# 08-AD9513-1.net
KiCad netlist of a schematic drawn in Altium Designer
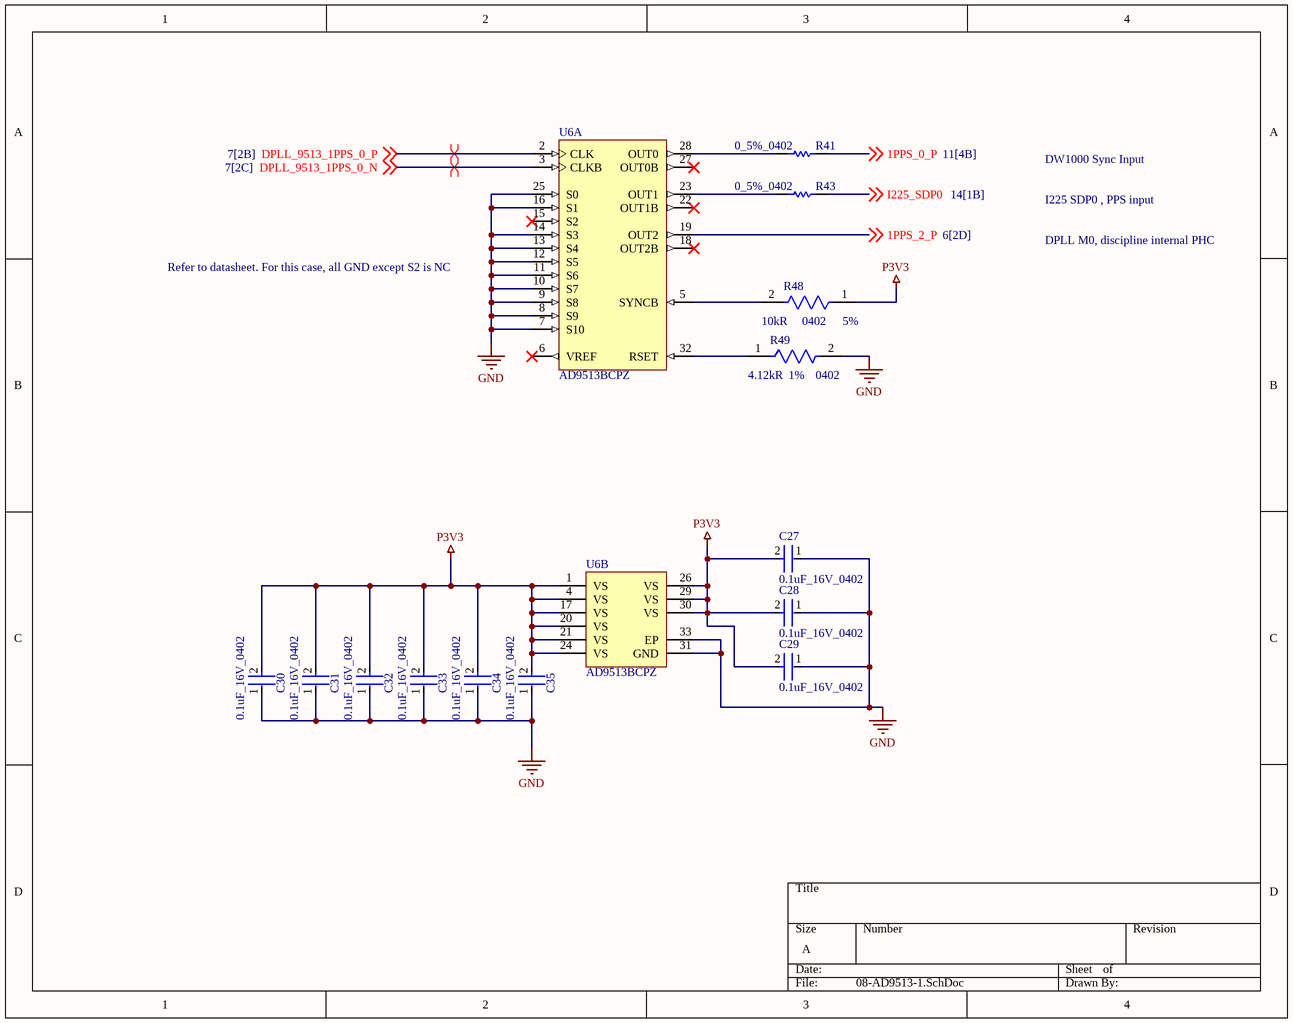
[diagram p0: 08-AD9513-1.SchDoc]

(export (version "E")
  (design (tool "Eeschema 10.0.6"))
  (components
    (comp (ref "C27")
      (value "0.1uF_16V_0402")
      (footprint "FP-GRM15-MFG")
      (description "CAP CER 0.1UF 16V X7R 0402")
      (fields (field (name "MANUFACTURER PART NUMBER") "GRM155R71C104KA88D") (field (name "TOLERANCE") "10%"))
      (libsource (lib "Altium Content Vault") (part "236180d848d6139a670b325ea6854c9"))
    )
    (comp (ref "C28")
      (value "0.1uF_16V_0402")
      (footprint "FP-GRM15-MFG")
      (description "CAP CER 0.1UF 16V X7R 0402")
      (fields (field (name "MANUFACTURER PART NUMBER") "GRM155R71C104KA88D") (field (name "TOLERANCE") "10%"))
      (libsource (lib "Altium Content Vault") (part "236180d848d6139a670b325ea6854c9"))
    )
    (comp (ref "C29")
      (value "0.1uF_16V_0402")
      (footprint "FP-GRM15-MFG")
      (description "CAP CER 0.1UF 16V X7R 0402")
      (fields (field (name "MANUFACTURER PART NUMBER") "GRM155R71C104KA88D") (field (name "TOLERANCE") "10%"))
      (libsource (lib "Altium Content Vault") (part "236180d848d6139a670b325ea6854c9"))
    )
    (comp (ref "C30")
      (value "0.1uF_16V_0402")
      (footprint "FP-GRM15-MFG")
      (description "CAP CER 0.1UF 16V X7R 0402")
      (fields (field (name "MANUFACTURER PART NUMBER") "GRM155R71C104KA88D") (field (name "TOLERANCE") "10%"))
      (libsource (lib "Altium Content Vault") (part "236180d848d6139a670b325ea6854c9"))
    )
    (comp (ref "C31")
      (value "0.1uF_16V_0402")
      (footprint "FP-GRM15-MFG")
      (description "CAP CER 0.1UF 16V X7R 0402")
      (fields (field (name "MANUFACTURER PART NUMBER") "GRM155R71C104KA88D") (field (name "TOLERANCE") "10%"))
      (libsource (lib "Altium Content Vault") (part "236180d848d6139a670b325ea6854c9"))
    )
    (comp (ref "C32")
      (value "0.1uF_16V_0402")
      (footprint "FP-GRM15-MFG")
      (description "CAP CER 0.1UF 16V X7R 0402")
      (fields (field (name "MANUFACTURER PART NUMBER") "GRM155R71C104KA88D") (field (name "TOLERANCE") "10%"))
      (libsource (lib "Altium Content Vault") (part "236180d848d6139a670b325ea6854c9"))
    )
    (comp (ref "C33")
      (value "0.1uF_16V_0402")
      (footprint "FP-GRM15-MFG")
      (description "CAP CER 0.1UF 16V X7R 0402")
      (fields (field (name "MANUFACTURER PART NUMBER") "GRM155R71C104KA88D") (field (name "TOLERANCE") "10%"))
      (libsource (lib "Altium Content Vault") (part "236180d848d6139a670b325ea6854c9"))
    )
    (comp (ref "C34")
      (value "0.1uF_16V_0402")
      (footprint "FP-GRM15-MFG")
      (description "CAP CER 0.1UF 16V X7R 0402")
      (fields (field (name "MANUFACTURER PART NUMBER") "GRM155R71C104KA88D") (field (name "TOLERANCE") "10%"))
      (libsource (lib "Altium Content Vault") (part "236180d848d6139a670b325ea6854c9"))
    )
    (comp (ref "C35")
      (value "0.1uF_16V_0402")
      (footprint "FP-GRM15-MFG")
      (description "CAP CER 0.1UF 16V X7R 0402")
      (fields (field (name "MANUFACTURER PART NUMBER") "GRM155R71C104KA88D") (field (name "TOLERANCE") "10%"))
      (libsource (lib "Altium Content Vault") (part "236180d848d6139a670b325ea6854c9"))
    )
    (comp (ref "R41")
      (value "0_5%_0402")
      (footprint "RESC1005X40X25LL10T10")
      (fields (field (name "MANUFACTURER") "KOA Speer") (field (name "PART NUMBER") "RK73Z1ETTP"))
      (libsource (lib "Altium Content Vault") (part "RES"))
    )
    (comp (ref "R43")
      (value "0_5%_0402")
      (footprint "RESC1005X40X25LL10T10")
      (fields (field (name "MANUFACTURER") "KOA Speer") (field (name "PART NUMBER") "RK73Z1ETTP"))
      (libsource (lib "Altium Content Vault") (part "RES"))
    )
    (comp (ref "R48")
      (value "CRCW040210K0JNED")
      (footprint "FP-CRCW0402-e3-IPC_B")
      (description "RES Thick Film, 10kΩ, 5%, 0.063W, 200ppm/°C, 0402")
      (fields
        (field (name "CASE/PACKAGE") "0402")
        (field (name "RESISTANCE") "10kR")
        (field (name "TOLERANCE") "5%")
      )
      (libsource (lib "Altium Content Vault") (part "1029c3af85768c4190bb7ad29bc67b5"))
    )
    (comp (ref "R49")
      (value "CRCW04024K12FKED")
      (footprint "FP-CRCW0402-e3-IPC_A")
      (description "RES Thick Film, 4.12kΩ, 1%, 0.063W, 100ppm/°C, 0402")
      (fields
        (field (name "RESISTANCE") "4.12kR")
        (field (name "CASE/PACKAGE") "0402")
        (field (name "TOLERANCE") "1%")
      )
      (libsource (lib "Altium Content Vault") (part "1029c3af85768c4190bb7ad29bc67b5"))
    )
    (comp (ref "U6")
      (value "AD9513BCPZ")
      (footprint "ADI-CP-32-2_N")
      (fields (field (name "MANUFACTURER") "Analog Devices"))
      (libsource (lib "Altium Content Vault") (part "ADI-AD9513-CP-32-2"))
    )
  )
  (nets
    (net (code "1") (name "1PPS_0_P") (class "Default")
      (node (ref "R41") (pin "2") (pinfunction "2_2") (pintype "passive"))
    )
    (net (code "2") (name "1PPS_2_P") (class "Default")
      (node (ref "U6") (pin "19") (pinfunction "OUT2_19") (pintype "output"))
    )
    (net (code "3") (name "DPLL_9513_1PPS_0_N") (class "Default")
      (node (ref "U6") (pin "3") (pinfunction "CLKB_3") (pintype "input"))
    )
    (net (code "4") (name "DPLL_9513_1PPS_0_P") (class "Default")
      (node (ref "U6") (pin "2") (pinfunction "CLK_2") (pintype "input"))
    )
    (net (code "5") (name "GND") (class "Default")
      (node (ref "C27") (pin "1") (pinfunction "1_1") (pintype "passive"))
      (node (ref "C28") (pin "1") (pinfunction "1_1") (pintype "passive"))
      (node (ref "C29") (pin "1") (pinfunction "1_1") (pintype "passive"))
      (node (ref "C30") (pin "1") (pinfunction "1_1") (pintype "passive"))
      (node (ref "C31") (pin "1") (pinfunction "1_1") (pintype "passive"))
      (node (ref "C32") (pin "1") (pinfunction "1_1") (pintype "passive"))
      (node (ref "C33") (pin "1") (pinfunction "1_1") (pintype "passive"))
      (node (ref "C34") (pin "1") (pinfunction "1_1") (pintype "passive"))
      (node (ref "C35") (pin "1") (pinfunction "1_1") (pintype "passive"))
      (node (ref "R49") (pin "2") (pinfunction "2_2") (pintype "passive"))
      (node (ref "U6") (pin "10") (pinfunction "S7_10") (pintype "input"))
      (node (ref "U6") (pin "11") (pinfunction "S6_11") (pintype "input"))
      (node (ref "U6") (pin "12") (pinfunction "S5_12") (pintype "input"))
      (node (ref "U6") (pin "13") (pinfunction "S4_13") (pintype "input"))
      (node (ref "U6") (pin "14") (pinfunction "S3_14") (pintype "input"))
      (node (ref "U6") (pin "16") (pinfunction "S1_16") (pintype "input"))
      (node (ref "U6") (pin "25") (pinfunction "S0_25") (pintype "input"))
      (node (ref "U6") (pin "31") (pinfunction "GND_31") (pintype "power_in"))
      (node (ref "U6") (pin "33") (pinfunction "EP_33") (pintype "power_in"))
      (node (ref "U6") (pin "7") (pinfunction "S10_7") (pintype "input"))
      (node (ref "U6") (pin "8") (pinfunction "S9_8") (pintype "input"))
      (node (ref "U6") (pin "9") (pinfunction "S8_9") (pintype "input"))
    )
    (net (code "6") (name "I225_SDP0") (class "Default")
      (node (ref "R43") (pin "2") (pinfunction "2_2") (pintype "passive"))
    )
    (net (code "7") (name "Net-(U6A-OUT0)") (class "Default")
      (node (ref "R41") (pin "1") (pinfunction "1_1") (pintype "passive"))
      (node (ref "U6") (pin "28") (pinfunction "OUT0_28") (pintype "output"))
    )
    (net (code "8") (name "Net-(U6A-OUT1)") (class "Default")
      (node (ref "R43") (pin "1") (pinfunction "1_1") (pintype "passive"))
      (node (ref "U6") (pin "23") (pinfunction "OUT1_23") (pintype "output"))
    )
    (net (code "9") (name "Net-(U6A-RSET)") (class "Default")
      (node (ref "R49") (pin "1") (pinfunction "1_1") (pintype "passive"))
      (node (ref "U6") (pin "32") (pinfunction "RSET_32") (pintype "input"))
    )
    (net (code "10") (name "Net-(U6A-SYNCB)") (class "Default")
      (node (ref "R48") (pin "2") (pinfunction "2_2") (pintype "passive"))
      (node (ref "U6") (pin "5") (pinfunction "SYNCB_5") (pintype "input"))
    )
    (net (code "11") (name "P3V3") (class "Default")
      (node (ref "C27") (pin "2") (pinfunction "2_2") (pintype "passive"))
      (node (ref "C28") (pin "2") (pinfunction "2_2") (pintype "passive"))
      (node (ref "C29") (pin "2") (pinfunction "2_2") (pintype "passive"))
      (node (ref "C30") (pin "2") (pinfunction "2_2") (pintype "passive"))
      (node (ref "C31") (pin "2") (pinfunction "2_2") (pintype "passive"))
      (node (ref "C32") (pin "2") (pinfunction "2_2") (pintype "passive"))
      (node (ref "C33") (pin "2") (pinfunction "2_2") (pintype "passive"))
      (node (ref "C34") (pin "2") (pinfunction "2_2") (pintype "passive"))
      (node (ref "C35") (pin "2") (pinfunction "2_2") (pintype "passive"))
      (node (ref "R48") (pin "1") (pinfunction "1_1") (pintype "passive"))
      (node (ref "U6") (pin "1") (pinfunction "VS_1") (pintype "power_in"))
      (node (ref "U6") (pin "17") (pinfunction "VS_17") (pintype "power_in"))
      (node (ref "U6") (pin "20") (pinfunction "VS_20") (pintype "power_in"))
      (node (ref "U6") (pin "21") (pinfunction "VS_21") (pintype "power_in"))
      (node (ref "U6") (pin "24") (pinfunction "VS_24") (pintype "power_in"))
      (node (ref "U6") (pin "26") (pinfunction "VS_26") (pintype "power_in"))
      (node (ref "U6") (pin "29") (pinfunction "VS_29") (pintype "power_in"))
      (node (ref "U6") (pin "30") (pinfunction "VS_30") (pintype "power_in"))
      (node (ref "U6") (pin "4") (pinfunction "VS_4") (pintype "power_in"))
    )
    (net (code "12") (name "unconnected-(U6A-OUT0B-Pad27)") (class "Default")
      (node (ref "U6") (pin "27") (pinfunction "OUT0B_27") (pintype "output+no_connect"))
    )
    (net (code "13") (name "unconnected-(U6A-OUT1B-Pad22)") (class "Default")
      (node (ref "U6") (pin "22") (pinfunction "OUT1B_22") (pintype "output+no_connect"))
    )
    (net (code "14") (name "unconnected-(U6A-OUT2B-Pad18)") (class "Default")
      (node (ref "U6") (pin "18") (pinfunction "OUT2B_18") (pintype "output+no_connect"))
    )
    (net (code "15") (name "unconnected-(U6A-S2-Pad15)") (class "Default")
      (node (ref "U6") (pin "15") (pinfunction "S2_15") (pintype "input+no_connect"))
    )
    (net (code "16") (name "unconnected-(U6A-VREF-Pad6)") (class "Default")
      (node (ref "U6") (pin "6") (pinfunction "VREF_6") (pintype "output+no_connect"))
    )
  )
)
